# Bluetooth_modul.net
KiCad netlist of a schematic drawn in Altium Designer
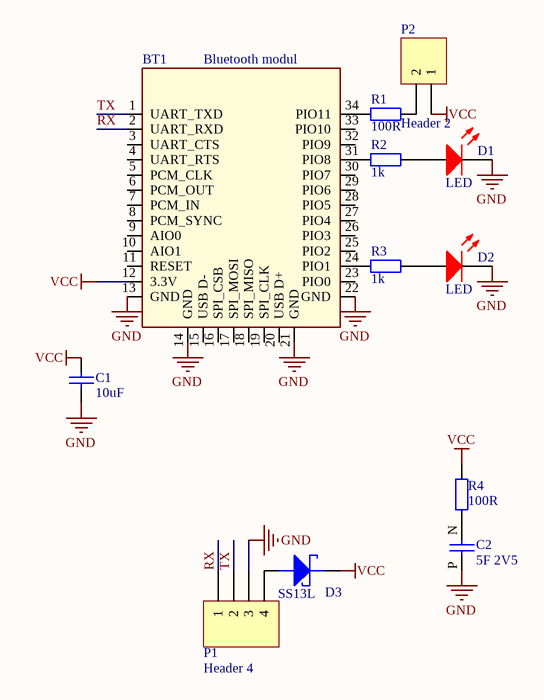
[diagram p0: Bluetooth modul.SchDoc]

(export (version "E")
  (design (tool "Eeschema 10.0.6"))
  (components
    (comp (ref "BT1")
      (value "Bluetooth modul")
      (footprint "BT_modul")
      (description "Wireless Bluetooth Transceiver Module RS232 / TTL")
      (libsource (lib "Modul") (part "Bluetooth modul"))
    )
    (comp (ref "C1")
      (value "10uF")
      (footprint "FP_0603_CAP_080")
      (description "Capacitor")
      (libsource (lib "Capacitor") (part "CAP"))
    )
    (comp (ref "C2")
      (value "5F 2V5")
      (footprint "Supercapacitor_10x20mm")
      (description "Supercap 5F 2V5")
      (libsource (lib "Capacitor") (part "Supercap 5F 2V5"))
    )
    (comp (ref "D1")
      (value "LED")
      (footprint "FP_0805_LED_RED")
      (description "Typical LED")
      (libsource (lib "Led_optical") (part "LED_R"))
    )
    (comp (ref "D2")
      (value "LED")
      (footprint "FP_0805_LED_RED")
      (description "Typical LED")
      (libsource (lib "Led_optical") (part "LED_R"))
    )
    (comp (ref "D3")
      (value "SS13L")
      (footprint "subsma")
      (description "NXP - PMEG3020EJ,115 - SCHOTTKY RECT 30V 2A SOD323F")
      (libsource (lib "Diode") (part "SCHOTTKY"))
    )
    (comp (ref "P1")
      (value "Header 4")
      (footprint "HDR1X4")
      (description "Header, 4-Pin")
      (fields (field (name "PUBLISHER") "Altium Limited"))
      (libsource (lib "Miscellaneous Connectors") (part "Header 4"))
    )
    (comp (ref "P2")
      (value "Header 2")
      (footprint "HDR1X2")
      (description "Header, 2-Pin")
      (fields (field (name "PUBLISHER") "Altium Limited"))
      (libsource (lib "Miscellaneous Connectors") (part "Header 2"))
    )
    (comp (ref "R1")
      (value "100R")
      (footprint "FP_0603_RES")
      (description "Resistor")
      (libsource (lib "") (part "RES_1"))
    )
    (comp (ref "R2")
      (value "1k")
      (footprint "FP_0603_RES")
      (description "Resistor")
      (libsource (lib "") (part "RES_1"))
    )
    (comp (ref "R3")
      (value "1k")
      (footprint "FP_0603_RES")
      (description "Resistor")
      (libsource (lib "") (part "RES_1"))
    )
    (comp (ref "R4")
      (value "100R")
      (footprint "FP_0603_RES")
      (description "Resistor")
      (libsource (lib "Resistor") (part "RES"))
    )
  )
  (nets
    (net (code "1") (name "/RX") (class "Default")
      (node (ref "BT1") (pin "2") (pinfunction "UART_RXD_2") (pintype "passive"))
      (node (ref "P1") (pin "1") (pinfunction "1_1") (pintype "passive"))
    )
    (net (code "2") (name "/TX") (class "Default")
      (node (ref "BT1") (pin "1") (pinfunction "UART_TXD_1") (pintype "passive"))
      (node (ref "P1") (pin "2") (pinfunction "2_2") (pintype "passive"))
    )
    (net (code "3") (name "GND") (class "Default")
      (node (ref "BT1") (pin "13") (pinfunction "GND_13") (pintype "passive"))
      (node (ref "BT1") (pin "14") (pinfunction "GND_14") (pintype "passive"))
      (node (ref "BT1") (pin "21") (pinfunction "GND_21") (pintype "passive"))
      (node (ref "BT1") (pin "22") (pinfunction "GND_22") (pintype "passive"))
      (node (ref "C1") (pin "1") (pinfunction "1_1") (pintype "passive"))
      (node (ref "C2") (pin "P") (pinfunction "P_P") (pintype "passive"))
      (node (ref "D1") (pin "K") (pinfunction "K_K") (pintype "passive"))
      (node (ref "D2") (pin "K") (pinfunction "K_K") (pintype "passive"))
      (node (ref "P1") (pin "3") (pinfunction "3_3") (pintype "passive"))
    )
    (net (code "4") (name "Net-(BT1-PIO1)") (class "Default")
      (node (ref "BT1") (pin "24") (pinfunction "PIO1_24") (pintype "passive"))
      (node (ref "R3") (pin "2") (pinfunction "2_2") (pintype "passive"))
    )
    (net (code "5") (name "Net-(BT1-PIO8)") (class "Default")
      (node (ref "BT1") (pin "31") (pinfunction "PIO8_31") (pintype "passive"))
      (node (ref "R2") (pin "2") (pinfunction "2_2") (pintype "passive"))
    )
    (net (code "6") (name "Net-(BT1-PIO11)") (class "Default")
      (node (ref "BT1") (pin "34") (pinfunction "PIO11_34") (pintype "passive"))
      (node (ref "R1") (pin "2") (pinfunction "2_2") (pintype "passive"))
    )
    (net (code "7") (name "Net-(C2-PadN)") (class "Default")
      (node (ref "C2") (pin "N") (pinfunction "N_N") (pintype "passive"))
      (node (ref "R4") (pin "1") (pinfunction "1_1") (pintype "passive"))
    )
    (net (code "8") (name "Net-(D1-PadA)") (class "Default")
      (node (ref "D1") (pin "A") (pinfunction "A_A") (pintype "passive"))
      (node (ref "R2") (pin "1") (pinfunction "1_1") (pintype "passive"))
    )
    (net (code "9") (name "Net-(D2-PadA)") (class "Default")
      (node (ref "D2") (pin "A") (pinfunction "A_A") (pintype "passive"))
      (node (ref "R3") (pin "1") (pinfunction "1_1") (pintype "passive"))
    )
    (net (code "10") (name "Net-(D3-PadA)") (class "Default")
      (node (ref "D3") (pin "A") (pinfunction "A_A") (pintype "passive"))
      (node (ref "P1") (pin "4") (pinfunction "4_4") (pintype "passive"))
    )
    (net (code "11") (name "Net-(P2-Pad2)") (class "Default")
      (node (ref "P2") (pin "2") (pinfunction "2_2") (pintype "passive"))
      (node (ref "R1") (pin "1") (pinfunction "1_1") (pintype "passive"))
    )
    (net (code "12") (name "VCC") (class "Default")
      (node (ref "BT1") (pin "12") (pinfunction "3.3V_12") (pintype "passive"))
      (node (ref "C1") (pin "2") (pinfunction "2_2") (pintype "passive"))
      (node (ref "D3") (pin "K") (pinfunction "K_K") (pintype "passive"))
      (node (ref "P2") (pin "1") (pinfunction "1_1") (pintype "passive"))
      (node (ref "R4") (pin "2") (pinfunction "2_2") (pintype "passive"))
    )
    (net (code "13") (name "unconnected-(BT1-AIO0-Pad9)") (class "Default")
      (node (ref "BT1") (pin "9") (pinfunction "AIO0_9") (pintype "passive"))
    )
    (net (code "14") (name "unconnected-(BT1-AIO1-Pad10)") (class "Default")
      (node (ref "BT1") (pin "10") (pinfunction "AIO1_10") (pintype "passive"))
    )
    (net (code "15") (name "unconnected-(BT1-PCM_CLK-Pad5)") (class "Default")
      (node (ref "BT1") (pin "5") (pinfunction "PCM_CLK_5") (pintype "passive"))
    )
    (net (code "16") (name "unconnected-(BT1-PCM_IN-Pad7)") (class "Default")
      (node (ref "BT1") (pin "7") (pinfunction "PCM_IN_7") (pintype "passive"))
    )
    (net (code "17") (name "unconnected-(BT1-PCM_OUT-Pad6)") (class "Default")
      (node (ref "BT1") (pin "6") (pinfunction "PCM_OUT_6") (pintype "passive"))
    )
    (net (code "18") (name "unconnected-(BT1-PCM_SYNC-Pad8)") (class "Default")
      (node (ref "BT1") (pin "8") (pinfunction "PCM_SYNC_8") (pintype "passive"))
    )
    (net (code "19") (name "unconnected-(BT1-PIO0-Pad23)") (class "Default")
      (node (ref "BT1") (pin "23") (pinfunction "PIO0_23") (pintype "passive"))
    )
    (net (code "20") (name "unconnected-(BT1-PIO2-Pad25)") (class "Default")
      (node (ref "BT1") (pin "25") (pinfunction "PIO2_25") (pintype "passive"))
    )
    (net (code "21") (name "unconnected-(BT1-PIO3-Pad26)") (class "Default")
      (node (ref "BT1") (pin "26") (pinfunction "PIO3_26") (pintype "passive"))
    )
    (net (code "22") (name "unconnected-(BT1-PIO4-Pad27)") (class "Default")
      (node (ref "BT1") (pin "27") (pinfunction "PIO4_27") (pintype "passive"))
    )
    (net (code "23") (name "unconnected-(BT1-PIO5-Pad28)") (class "Default")
      (node (ref "BT1") (pin "28") (pinfunction "PIO5_28") (pintype "passive"))
    )
    (net (code "24") (name "unconnected-(BT1-PIO6-Pad29)") (class "Default")
      (node (ref "BT1") (pin "29") (pinfunction "PIO6_29") (pintype "passive"))
    )
    (net (code "25") (name "unconnected-(BT1-PIO7-Pad30)") (class "Default")
      (node (ref "BT1") (pin "30") (pinfunction "PIO7_30") (pintype "passive"))
    )
    (net (code "26") (name "unconnected-(BT1-PIO9-Pad32)") (class "Default")
      (node (ref "BT1") (pin "32") (pinfunction "PIO9_32") (pintype "passive"))
    )
    (net (code "27") (name "unconnected-(BT1-PIO10-Pad33)") (class "Default")
      (node (ref "BT1") (pin "33") (pinfunction "PIO10_33") (pintype "passive"))
    )
    (net (code "28") (name "unconnected-(BT1-RESET-Pad11)") (class "Default")
      (node (ref "BT1") (pin "11") (pinfunction "RESET_11") (pintype "passive"))
    )
    (net (code "29") (name "unconnected-(BT1-SPI_CLK-Pad19)") (class "Default")
      (node (ref "BT1") (pin "19") (pinfunction "SPI_CLK_19") (pintype "passive"))
    )
    (net (code "30") (name "unconnected-(BT1-SPI_CSB-Pad16)") (class "Default")
      (node (ref "BT1") (pin "16") (pinfunction "SPI_CSB_16") (pintype "passive"))
    )
    (net (code "31") (name "unconnected-(BT1-SPI_MISO-Pad18)") (class "Default")
      (node (ref "BT1") (pin "18") (pinfunction "SPI_MISO_18") (pintype "passive"))
    )
    (net (code "32") (name "unconnected-(BT1-SPI_MOSI-Pad17)") (class "Default")
      (node (ref "BT1") (pin "17") (pinfunction "SPI_MOSI_17") (pintype "passive"))
    )
    (net (code "33") (name "unconnected-(BT1-UART_CTS-Pad3)") (class "Default")
      (node (ref "BT1") (pin "3") (pinfunction "UART_CTS_3") (pintype "passive"))
    )
    (net (code "34") (name "unconnected-(BT1-UART_RTS-Pad4)") (class "Default")
      (node (ref "BT1") (pin "4") (pinfunction "UART_RTS_4") (pintype "passive"))
    )
    (net (code "35") (name "unconnected-(BT1-USB_D+-Pad20)") (class "Default")
      (node (ref "BT1") (pin "20") (pinfunction "USB_D+_20") (pintype "passive"))
    )
    (net (code "36") (name "unconnected-(BT1-USB_D--Pad15)") (class "Default")
      (node (ref "BT1") (pin "15") (pinfunction "USB_D-_15") (pintype "passive"))
    )
  )
)
